# scheme.net
KiCad netlist of a schematic drawn in EAGLE
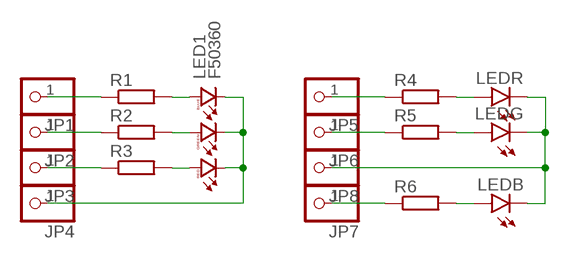
[diagram p0: schematic, sheet 1]

(export (version "E")
  (design (tool "Eeschema 10.0.6"))
  (components
    (comp (ref "JP1")
      (value "PINHD-1X1")
      (footprint "eagle-import:1X01")
      (libsource (lib "eagle-import") (part "PINHD-1X1"))
    )
    (comp (ref "JP2")
      (value "PINHD-1X1")
      (footprint "eagle-import:1X01")
      (libsource (lib "eagle-import") (part "PINHD-1X1"))
    )
    (comp (ref "JP3")
      (value "PINHD-1X1")
      (footprint "eagle-import:1X01")
      (libsource (lib "eagle-import") (part "PINHD-1X1"))
    )
    (comp (ref "JP4")
      (value "PINHD-1X1")
      (footprint "eagle-import:1X01")
      (libsource (lib "eagle-import") (part "PINHD-1X1"))
    )
    (comp (ref "JP5")
      (value "PINHD-1X1")
      (footprint "eagle-import:1X01")
      (libsource (lib "eagle-import") (part "PINHD-1X1"))
    )
    (comp (ref "JP6")
      (value "PINHD-1X1")
      (footprint "eagle-import:1X01")
      (libsource (lib "eagle-import") (part "PINHD-1X1"))
    )
    (comp (ref "JP7")
      (value "PINHD-1X1")
      (footprint "eagle-import:1X01")
      (libsource (lib "eagle-import") (part "PINHD-1X1"))
    )
    (comp (ref "JP8")
      (value "PINHD-1X1")
      (footprint "eagle-import:1X01")
      (libsource (lib "eagle-import") (part "PINHD-1X1"))
    )
    (comp (ref "LED1")
      (value "F50360")
      (footprint "eagle-import:F50360")
      (libsource (lib "eagle-import") (part "F50360"))
    )
    (comp (ref "LEDB")
      (value "LED10MM")
      (footprint "eagle-import:LED10MM")
      (libsource (lib "eagle-import") (part "LED10MM"))
    )
    (comp (ref "LEDG")
      (value "LED10MM")
      (footprint "eagle-import:LED10MM")
      (libsource (lib "eagle-import") (part "LED10MM"))
    )
    (comp (ref "LEDR")
      (value "LED10MM")
      (footprint "eagle-import:LED10MM")
      (libsource (lib "eagle-import") (part "LED10MM"))
    )
    (comp (ref "R1")
      (value "R-EU_0414/15")
      (footprint "eagle-import:0414_15")
      (libsource (lib "eagle-import") (part "R-EU_0414/15"))
    )
    (comp (ref "R2")
      (value "R-EU_0414/15")
      (footprint "eagle-import:0414_15")
      (libsource (lib "eagle-import") (part "R-EU_0414/15"))
    )
    (comp (ref "R3")
      (value "R-EU_0414/15")
      (footprint "eagle-import:0414_15")
      (libsource (lib "eagle-import") (part "R-EU_0414/15"))
    )
    (comp (ref "R4")
      (value "R-EU_0414/15")
      (footprint "eagle-import:0414_15")
      (libsource (lib "eagle-import") (part "R-EU_0414/15"))
    )
    (comp (ref "R5")
      (value "R-EU_0414/15")
      (footprint "eagle-import:0414_15")
      (libsource (lib "eagle-import") (part "R-EU_0414/15"))
    )
    (comp (ref "R6")
      (value "R-EU_0414/15")
      (footprint "eagle-import:0414_15")
      (libsource (lib "eagle-import") (part "R-EU_0414/15"))
    )
  )
  (nets
    (net (code "1") (name "Net-(JP1-Pad1)") (class "Default")
      (node (ref "JP1") (pin "1") (pinfunction "1_1") (pintype "passive"))
      (node (ref "R1") (pin "1") (pinfunction "1_1") (pintype "passive"))
    )
    (net (code "2") (name "Net-(JP2-Pad1)") (class "Default")
      (node (ref "JP2") (pin "1") (pinfunction "1_1") (pintype "passive"))
      (node (ref "R2") (pin "1") (pinfunction "1_1") (pintype "passive"))
    )
    (net (code "3") (name "Net-(JP3-Pad1)") (class "Default")
      (node (ref "JP3") (pin "1") (pinfunction "1_1") (pintype "passive"))
      (node (ref "R3") (pin "1") (pinfunction "1_1") (pintype "passive"))
    )
    (net (code "4") (name "Net-(JP4-Pad1)") (class "Default")
      (node (ref "JP4") (pin "1") (pinfunction "1_1") (pintype "passive"))
      (node (ref "LED1") (pin "BC") (pinfunction "BC_BC") (pintype "passive"))
      (node (ref "LED1") (pin "GC") (pinfunction "GC_GC") (pintype "passive"))
      (node (ref "LED1") (pin "RC") (pinfunction "RC_RC") (pintype "passive"))
    )
    (net (code "5") (name "Net-(JP5-Pad1)") (class "Default")
      (node (ref "JP5") (pin "1") (pinfunction "1_1") (pintype "passive"))
      (node (ref "R4") (pin "1") (pinfunction "1_1") (pintype "passive"))
    )
    (net (code "6") (name "Net-(JP6-Pad1)") (class "Default")
      (node (ref "JP6") (pin "1") (pinfunction "1_1") (pintype "passive"))
      (node (ref "R5") (pin "1") (pinfunction "1_1") (pintype "passive"))
    )
    (net (code "7") (name "Net-(JP7-Pad1)") (class "Default")
      (node (ref "JP7") (pin "1") (pinfunction "1_1") (pintype "passive"))
      (node (ref "R6") (pin "1") (pinfunction "1_1") (pintype "passive"))
    )
    (net (code "8") (name "Net-(LED1-PadBA)") (class "Default")
      (node (ref "LED1") (pin "BA") (pinfunction "BA_BA") (pintype "passive"))
      (node (ref "R1") (pin "2") (pinfunction "2_2") (pintype "passive"))
    )
    (net (code "9") (name "Net-(LED1-PadGA)") (class "Default")
      (node (ref "LED1") (pin "GA") (pinfunction "GA_GA") (pintype "passive"))
      (node (ref "R2") (pin "2") (pinfunction "2_2") (pintype "passive"))
    )
    (net (code "10") (name "Net-(LED1-PadRA)") (class "Default")
      (node (ref "LED1") (pin "RA") (pinfunction "RA_RA") (pintype "passive"))
      (node (ref "R3") (pin "2") (pinfunction "2_2") (pintype "passive"))
    )
    (net (code "11") (name "Net-(LEDB-C)") (class "Default")
      (node (ref "JP8") (pin "1") (pinfunction "1_1") (pintype "passive"))
      (node (ref "LEDB") (pin "K") (pinfunction "C_K") (pintype "passive"))
      (node (ref "LEDG") (pin "K") (pinfunction "C_K") (pintype "passive"))
      (node (ref "LEDR") (pin "K") (pinfunction "C_K") (pintype "passive"))
    )
    (net (code "12") (name "Net-(LEDB-PadA)") (class "Default")
      (node (ref "LEDB") (pin "A") (pinfunction "A_A") (pintype "passive"))
      (node (ref "R6") (pin "2") (pinfunction "2_2") (pintype "passive"))
    )
    (net (code "13") (name "Net-(LEDG-PadA)") (class "Default")
      (node (ref "LEDG") (pin "A") (pinfunction "A_A") (pintype "passive"))
      (node (ref "R5") (pin "2") (pinfunction "2_2") (pintype "passive"))
    )
    (net (code "14") (name "Net-(LEDR-PadA)") (class "Default")
      (node (ref "LEDR") (pin "A") (pinfunction "A_A") (pintype "passive"))
      (node (ref "R4") (pin "2") (pinfunction "2_2") (pintype "passive"))
    )
  )
)
